# Audio.net
KiCad netlist of a schematic drawn in Altium Designer
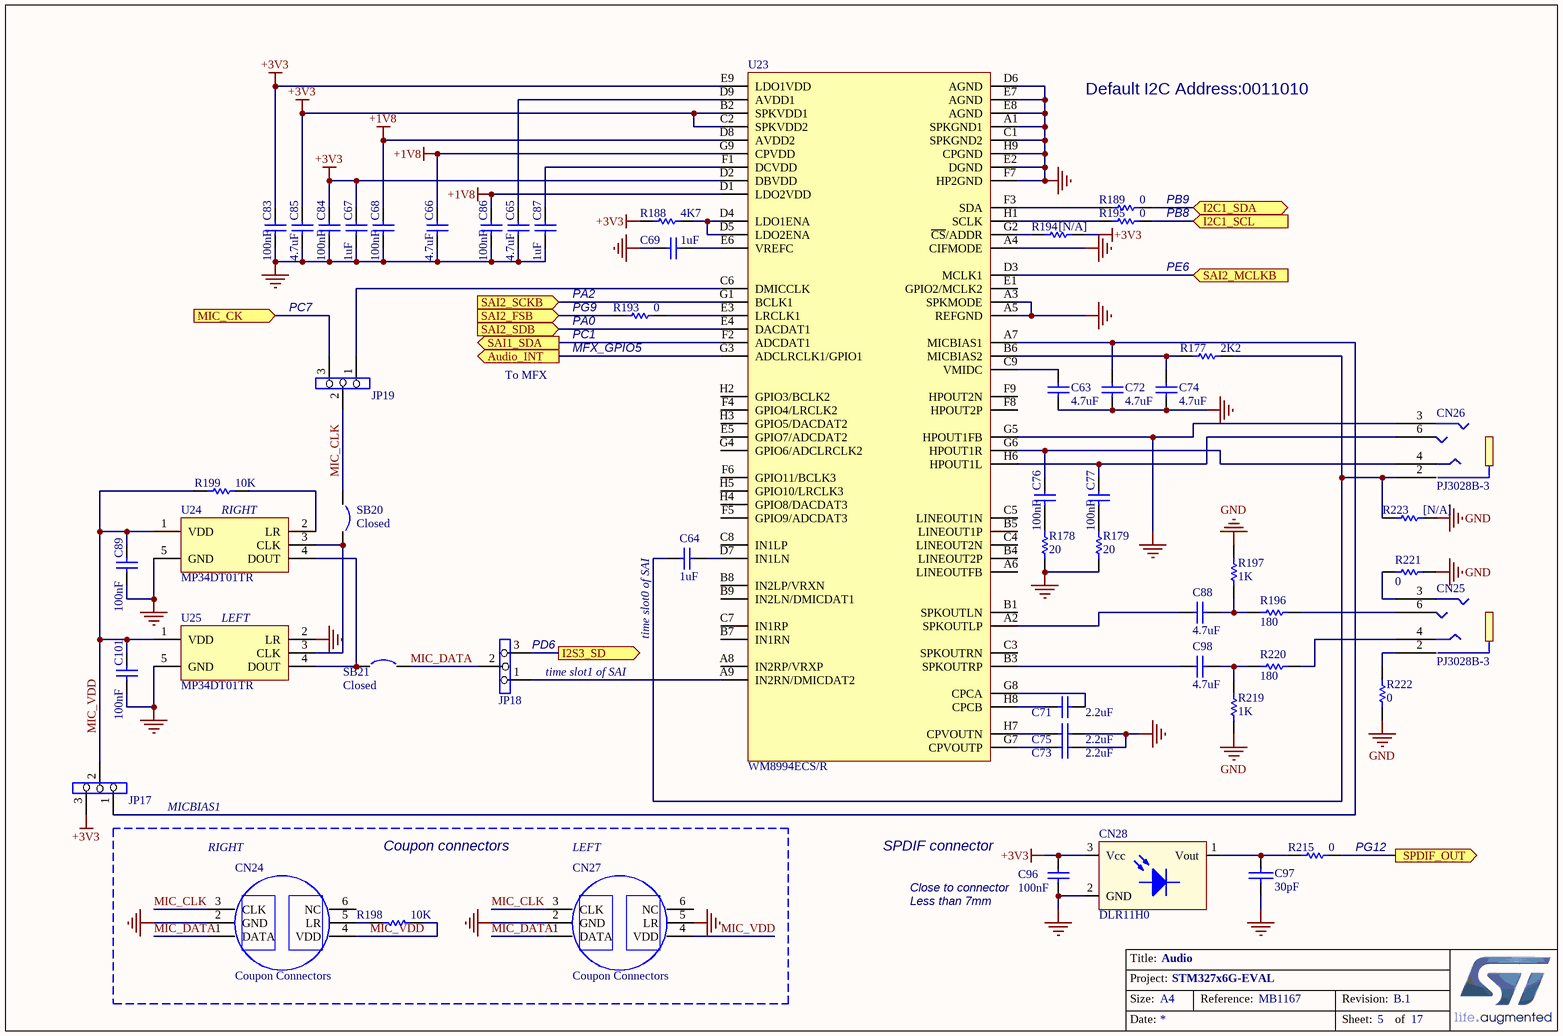
[diagram p0: Audio.SchDoc]

(export (version "E")
  (design (tool "Eeschema 10.0.6"))
  (components
    (comp (ref "C63")
      (value "4.7uF")
      (footprint "0603C")
      (description "Capacitor")
      (fields (field (name "PUBLISHER") "Altium Limited"))
      (libsource (lib "Miscellaneous Devices") (part "Cap"))
    )
    (comp (ref "C64")
      (value "1uF")
      (footprint "0603C")
      (description "Capacitor")
      (fields (field (name "PUBLISHER") "Altium Limited"))
      (libsource (lib "Miscellaneous Devices") (part "CAP"))
    )
    (comp (ref "C65")
      (value "4.7uF")
      (footprint "0603C")
      (description "Capacitor")
      (fields (field (name "PUBLISHER") "Altium Limited"))
      (libsource (lib "Miscellaneous Devices") (part "Cap"))
    )
    (comp (ref "C66")
      (value "4.7uF")
      (footprint "0603C")
      (description "Capacitor")
      (fields (field (name "PUBLISHER") "Altium Limited"))
      (libsource (lib "Miscellaneous Devices") (part "Cap"))
    )
    (comp (ref "C67")
      (value "1uF")
      (footprint "0603C")
      (description "Capacitor")
      (fields (field (name "PUBLISHER") "Altium Limited"))
      (libsource (lib "Miscellaneous Devices") (part "CAP"))
    )
    (comp (ref "C68")
      (value "100nF")
      (footprint "0603C")
      (description "Capacitor")
      (fields (field (name "PUBLISHER") "Altium Limited"))
      (libsource (lib "Miscellaneous Devices") (part "Cap"))
    )
    (comp (ref "C69")
      (value "1uF")
      (footprint "0603C")
      (description "Capacitor")
      (fields (field (name "PUBLISHER") "Altium Limited"))
      (libsource (lib "Miscellaneous Devices") (part "CAP"))
    )
    (comp (ref "C71")
      (value "2.2uF")
      (footprint "0603C")
      (description "Capacitor")
      (fields (field (name "PUBLISHER") "Altium Limited"))
      (libsource (lib "Miscellaneous Devices") (part "CAP"))
    )
    (comp (ref "C72")
      (value "4.7uF")
      (footprint "0603C")
      (description "Capacitor")
      (fields (field (name "PUBLISHER") "Altium Limited"))
      (libsource (lib "Miscellaneous Devices") (part "Cap"))
    )
    (comp (ref "C73")
      (value "2.2uF")
      (footprint "0603C")
      (description "Capacitor")
      (fields (field (name "PUBLISHER") "Altium Limited"))
      (libsource (lib "Miscellaneous Devices") (part "CAP"))
    )
    (comp (ref "C74")
      (value "4.7uF")
      (footprint "0603C")
      (description "Capacitor")
      (fields (field (name "PUBLISHER") "Altium Limited"))
      (libsource (lib "Miscellaneous Devices") (part "Cap"))
    )
    (comp (ref "C75")
      (value "2.2uF")
      (footprint "0603C")
      (description "Capacitor")
      (fields (field (name "PUBLISHER") "Altium Limited"))
      (libsource (lib "Miscellaneous Devices") (part "CAP"))
    )
    (comp (ref "C76")
      (value "100nF")
      (footprint "0603C")
      (description "Capacitor")
      (fields (field (name "PUBLISHER") "Altium Limited"))
      (libsource (lib "Miscellaneous Devices") (part "Cap"))
    )
    (comp (ref "C77")
      (value "100nF")
      (footprint "0603C")
      (description "Capacitor")
      (fields (field (name "PUBLISHER") "Altium Limited"))
      (libsource (lib "Miscellaneous Devices") (part "Cap"))
    )
    (comp (ref "C83")
      (value "100nF")
      (footprint "0603C")
      (description "Capacitor")
      (fields (field (name "PUBLISHER") "Altium Limited"))
      (libsource (lib "Miscellaneous Devices") (part "Cap"))
    )
    (comp (ref "C84")
      (value "100nF")
      (footprint "0603C")
      (description "Capacitor")
      (fields (field (name "PUBLISHER") "Altium Limited"))
      (libsource (lib "Miscellaneous Devices") (part "Cap"))
    )
    (comp (ref "C85")
      (value "4.7uF")
      (footprint "0603C")
      (description "Capacitor")
      (fields (field (name "PUBLISHER") "Altium Limited"))
      (libsource (lib "Miscellaneous Devices") (part "Cap"))
    )
    (comp (ref "C86")
      (value "100nF")
      (footprint "0603C")
      (description "Capacitor")
      (fields (field (name "PUBLISHER") "Altium Limited"))
      (libsource (lib "Miscellaneous Devices") (part "Cap"))
    )
    (comp (ref "C87")
      (value "1uF")
      (footprint "0603C")
      (description "Capacitor")
      (fields (field (name "PUBLISHER") "Altium Limited"))
      (libsource (lib "Miscellaneous Devices") (part "CAP"))
    )
    (comp (ref "C88")
      (value "4.7uF")
      (footprint "0603C")
      (description "Capacitor")
      (fields (field (name "PUBLISHER") "Altium Limited"))
      (libsource (lib "Miscellaneous Devices") (part "Cap"))
    )
    (comp (ref "C89")
      (value "100nF")
      (footprint "0603C")
      (description "Capacitor")
      (fields (field (name "PUBLISHER") "Altium Limited"))
      (libsource (lib "Miscellaneous Devices") (part "Cap"))
    )
    (comp (ref "C96")
      (value "100nF")
      (footprint "0603C")
      (description "Capacitor")
      (fields (field (name "PUBLISHER") "Altium Limited"))
      (libsource (lib "Miscellaneous Devices") (part "Cap"))
    )
    (comp (ref "C97")
      (value "30pF")
      (footprint "0603C")
      (description "Capacitor")
      (libsource (lib "*") (part "CAP"))
    )
    (comp (ref "C98")
      (value "4.7uF")
      (footprint "0603C")
      (description "Capacitor")
      (fields (field (name "PUBLISHER") "Altium Limited"))
      (libsource (lib "Miscellaneous Devices") (part "Cap"))
    )
    (comp (ref "C101")
      (value "100nF")
      (footprint "0603C")
      (description "Capacitor")
      (fields (field (name "PUBLISHER") "Altium Limited"))
      (libsource (lib "Miscellaneous Devices") (part "Cap"))
    )
    (comp (ref "CN24")
      (value "Coupon Connectors")
      (footprint "Coupon")
      (description "Header, 3-Pin, Single row")
      (fields (field (name "PUBLISHER") "Altium Limited"))
      (libsource (lib "MB1167") (part "Coupon Connectors"))
    )
    (comp (ref "CN25") (value "PJ3028B-3") (footprint "PJ3028B") (libsource (lib "MB786") (part "PJ3028B-3")))
    (comp (ref "CN26") (value "PJ3028B-3") (footprint "PJ3028B") (libsource (lib "MB786") (part "PJ3028B-3")))
    (comp (ref "CN27")
      (value "Coupon Connectors")
      (footprint "Coupon")
      (description "Header, 3-Pin, Single row")
      (fields (field (name "PUBLISHER") "Altium Limited"))
      (libsource (lib "MB1167") (part "Coupon Connectors"))
    )
    (comp (ref "CN28")
      (value "DLR11H0")
      (footprint "CONN_DLR11H0")
      (libsource (lib "MB1167_1") (part "OPTO"))
    )
    (comp (ref "JP17") (value "~") (footprint "SIP3") (libsource (lib "STR910_SCHLIB") (part "Jumper3")))
    (comp (ref "JP18") (value "~") (footprint "SIP3") (libsource (lib "STR910_SCHLIB") (part "Jumper3")))
    (comp (ref "JP19") (value "~") (footprint "SIP3") (libsource (lib "STR910_SCHLIB") (part "Jumper3")))
    (comp (ref "R177")
      (value "2K2")
      (footprint "0603R")
      (description "Resistor")
      (fields (field (name "PUBLISHER") "Altium Limited"))
      (libsource (lib "Miscellaneous Devices") (part "Res1"))
    )
    (comp (ref "R178")
      (value "20")
      (footprint "0603R")
      (description "Resistor")
      (fields (field (name "PUBLISHER") "Altium Limited"))
      (libsource (lib "Miscellaneous Devices") (part "Res1"))
    )
    (comp (ref "R179")
      (value "20")
      (footprint "0603R")
      (description "Resistor")
      (fields (field (name "PUBLISHER") "Altium Limited"))
      (libsource (lib "Miscellaneous Devices") (part "Res1"))
    )
    (comp (ref "R188")
      (value "4K7")
      (footprint "0603R")
      (description "Resistor")
      (fields (field (name "PUBLISHER") "Altium Limited"))
      (libsource (lib "Miscellaneous Devices") (part "Res1"))
    )
    (comp (ref "R189")
      (value "0")
      (footprint "0603R")
      (description "Resistor")
      (fields (field (name "PUBLISHER") "Altium Limited"))
      (libsource (lib "Miscellaneous Devices") (part "Res1"))
    )
    (comp (ref "R193")
      (value "0")
      (footprint "0603R")
      (description "Resistor")
      (fields (field (name "PUBLISHER") "Altium Limited"))
      (libsource (lib "Miscellaneous Devices") (part "Res1"))
    )
    (comp (ref "R194")
      (value "[N/A]")
      (footprint "0603R")
      (description "Resistor")
      (fields (field (name "PUBLISHER") "Altium Limited"))
      (libsource (lib "Miscellaneous Devices") (part "Res1"))
    )
    (comp (ref "R195")
      (value "0")
      (footprint "0603R")
      (description "Resistor")
      (fields (field (name "PUBLISHER") "Altium Limited"))
      (libsource (lib "Miscellaneous Devices") (part "Res1"))
    )
    (comp (ref "R196")
      (value "180")
      (footprint "0402R")
      (description "Resistor")
      (fields (field (name "PUBLISHER") "Altium Limited"))
      (libsource (lib "Miscellaneous Devices") (part "Res1"))
    )
    (comp (ref "R197")
      (value "1K")
      (footprint "0402R")
      (description "Resistor")
      (fields (field (name "PUBLISHER") "Altium Limited"))
      (libsource (lib "Miscellaneous Devices") (part "Res1"))
    )
    (comp (ref "R198")
      (value "10K")
      (footprint "0603R")
      (description "Resistor")
      (fields (field (name "PUBLISHER") "Altium Limited"))
      (libsource (lib "Miscellaneous Devices") (part "Res1"))
    )
    (comp (ref "R199")
      (value "10K")
      (footprint "0603R")
      (description "Resistor")
      (fields (field (name "PUBLISHER") "Altium Limited"))
      (libsource (lib "Miscellaneous Devices") (part "Res1"))
    )
    (comp (ref "R215")
      (value "0")
      (footprint "0603R")
      (description "Resistor")
      (fields (field (name "PUBLISHER") "Altium Limited"))
      (libsource (lib "Miscellaneous Devices") (part "Res1"))
    )
    (comp (ref "R219")
      (value "1K")
      (footprint "0402R")
      (description "Resistor")
      (fields (field (name "PUBLISHER") "Altium Limited"))
      (libsource (lib "Miscellaneous Devices") (part "Res1"))
    )
    (comp (ref "R220")
      (value "180")
      (footprint "0402R")
      (description "Resistor")
      (fields (field (name "PUBLISHER") "Altium Limited"))
      (libsource (lib "Miscellaneous Devices") (part "Res1"))
    )
    (comp (ref "R221")
      (value "0")
      (footprint "0603R")
      (description "Resistor")
      (fields (field (name "PUBLISHER") "Altium Limited"))
      (libsource (lib "Miscellaneous Devices") (part "Res1"))
    )
    (comp (ref "R222")
      (value "0")
      (footprint "0603R")
      (description "Resistor")
      (fields (field (name "PUBLISHER") "Altium Limited"))
      (libsource (lib "Miscellaneous Devices") (part "Res1"))
    )
    (comp (ref "R223")
      (value "[N/A]")
      (footprint "0603R")
      (description "Resistor")
      (fields (field (name "PUBLISHER") "Altium Limited"))
      (libsource (lib "Miscellaneous Devices") (part "Res1"))
    )
    (comp (ref "SB20")
      (value "Closed")
      (footprint "SB_0603")
      (description "Circuit Breaker")
      (fields (field (name "PUBLISHER") "Altium Limited"))
      (libsource (lib "MB1167") (part "Circuit Breaker_close"))
    )
    (comp (ref "SB21")
      (value "Closed")
      (footprint "SB_0603")
      (description "Circuit Breaker")
      (fields (field (name "PUBLISHER") "Altium Limited"))
      (libsource (lib "MB1167") (part "Circuit Breaker_close"))
    )
    (comp (ref "U23")
      (value "WM8994ECS/R")
      (footprint "BGA72_0R5_4R5X4")
      (libsource (lib "mb1045") (part "WM8994ECS/R"))
    )
    (comp (ref "U24")
      (value "MP34DT01TR")
      (footprint "MP34DT01TR")
      (description "MEMS audio sensor")
      (fields (field (name "PUBLISHER") "Altium Limited"))
      (libsource (lib "mb1045") (part "MP34DT01TR"))
    )
    (comp (ref "U25")
      (value "MP34DT01TR")
      (footprint "MP34DT01TR")
      (description "MEMS audio sensor")
      (fields (field (name "PUBLISHER") "Altium Limited"))
      (libsource (lib "mb1045") (part "MP34DT01TR"))
    )
  )
  (nets
    (net (code "1") (name "+1V8") (class "Default")
      (node (ref "C66") (pin "1") (pinfunction "1_1") (pintype "passive"))
      (node (ref "C68") (pin "1") (pinfunction "1_1") (pintype "passive"))
      (node (ref "C86") (pin "1") (pinfunction "1_1") (pintype "passive"))
      (node (ref "U23") (pin "D1") (pinfunction "LDO2VDD_D1") (pintype "passive"))
      (node (ref "U23") (pin "D8") (pinfunction "AVDD2_D8") (pintype "passive"))
      (node (ref "U23") (pin "G9") (pinfunction "CPVDD_G9") (pintype "passive"))
    )
    (net (code "2") (name "+3V3") (class "Default")
      (node (ref "C67") (pin "1") (pinfunction "1_1") (pintype "passive"))
      (node (ref "C83") (pin "1") (pinfunction "1_1") (pintype "passive"))
      (node (ref "C84") (pin "1") (pinfunction "1_1") (pintype "passive"))
      (node (ref "C85") (pin "1") (pinfunction "1_1") (pintype "passive"))
      (node (ref "C96") (pin "2") (pinfunction "2_2") (pintype "passive"))
      (node (ref "CN28") (pin "3") (pinfunction "Vcc_3") (pintype "passive"))
      (node (ref "JP17") (pin "3") (pintype "passive"))
      (node (ref "R188") (pin "2") (pinfunction "2_2") (pintype "passive"))
      (node (ref "R194") (pin "1") (pinfunction "1_1") (pintype "passive"))
      (node (ref "U23") (pin "B2") (pinfunction "SPKVDD1_B2") (pintype "passive"))
      (node (ref "U23") (pin "C2") (pinfunction "SPKVDD2_C2") (pintype "passive"))
      (node (ref "U23") (pin "D2") (pinfunction "DBVDD_D2") (pintype "passive"))
      (node (ref "U23") (pin "E9") (pinfunction "LDO1VDD_E9") (pintype "passive"))
    )
    (net (code "3") (name "/Audio_INT") (class "Default")
      (node (ref "U23") (pin "G3") (pinfunction "ADCLRCLK1/GPIO1_G3") (pintype "passive"))
    )
    (net (code "4") (name "/I2C1_SCL") (class "Default")
      (node (ref "R195") (pin "1") (pinfunction "1_1") (pintype "passive"))
    )
    (net (code "5") (name "/I2C1_SDA") (class "Default")
      (node (ref "R189") (pin "1") (pinfunction "1_1") (pintype "passive"))
    )
    (net (code "6") (name "/I2S3_SD") (class "Default") (node (ref "JP18") (pin "3") (pintype "passive")))
    (net (code "7") (name "/MIC_CK") (class "Default") (node (ref "JP19") (pin "3") (pintype "passive")))
    (net (code "8") (name "/MIC_CLK") (class "Default")
      (node (ref "CN24") (pin "3") (pinfunction "CLK_3") (pintype "passive"))
      (node (ref "CN27") (pin "3") (pinfunction "CLK_3") (pintype "passive"))
      (node (ref "JP19") (pin "2") (pintype "passive"))
      (node (ref "SB20") (pin "1") (pinfunction "1_1") (pintype "passive"))
    )
    (net (code "9") (name "/MIC_DATA") (class "Default")
      (node (ref "CN24") (pin "1") (pinfunction "DATA_1") (pintype "passive"))
      (node (ref "CN27") (pin "1") (pinfunction "DATA_1") (pintype "passive"))
      (node (ref "JP18") (pin "2") (pintype "passive"))
      (node (ref "SB21") (pin "2") (pinfunction "2_2") (pintype "passive"))
    )
    (net (code "10") (name "/MIC_VDD") (class "Default")
      (node (ref "C101") (pin "1") (pinfunction "1_1") (pintype "passive"))
      (node (ref "C89") (pin "1") (pinfunction "1_1") (pintype "passive"))
      (node (ref "CN24") (pin "4") (pinfunction "VDD_4") (pintype "passive"))
      (node (ref "CN27") (pin "4") (pinfunction "VDD_4") (pintype "passive"))
      (node (ref "JP17") (pin "2") (pintype "passive"))
      (node (ref "R198") (pin "2") (pinfunction "2_2") (pintype "passive"))
      (node (ref "R199") (pin "2") (pinfunction "2_2") (pintype "passive"))
      (node (ref "U24") (pin "1") (pinfunction "VDD_1") (pintype "passive"))
      (node (ref "U25") (pin "1") (pinfunction "VDD_1") (pintype "passive"))
    )
    (net (code "11") (name "/SAI1_SDA") (class "Default")
      (node (ref "U23") (pin "F2") (pinfunction "ADCDAT1_F2") (pintype "passive"))
    )
    (net (code "12") (name "/SAI2_FSB") (class "Default")
      (node (ref "R193") (pin "2") (pinfunction "2_2") (pintype "passive"))
    )
    (net (code "13") (name "/SAI2_MCLKB") (class "Default")
      (node (ref "U23") (pin "D3") (pinfunction "MCLK1_D3") (pintype "passive"))
    )
    (net (code "14") (name "/SAI2_SCKB") (class "Default")
      (node (ref "U23") (pin "G1") (pinfunction "BCLK1_G1") (pintype "passive"))
    )
    (net (code "15") (name "/SAI2_SDB") (class "Default")
      (node (ref "U23") (pin "E4") (pinfunction "DACDAT1_E4") (pintype "passive"))
    )
    (net (code "16") (name "/SPDIF_OUT") (class "Default")
      (node (ref "R215") (pin "1") (pinfunction "1_1") (pintype "passive"))
    )
    (net (code "17") (name "GND") (class "Default")
      (node (ref "C101") (pin "2") (pinfunction "2_2") (pintype "passive"))
      (node (ref "C63") (pin "1") (pinfunction "1_1") (pintype "passive"))
      (node (ref "C65") (pin "2") (pinfunction "2_2") (pintype "passive"))
      (node (ref "C66") (pin "2") (pinfunction "2_2") (pintype "passive"))
      (node (ref "C67") (pin "2") (pinfunction "2_2") (pintype "passive"))
      (node (ref "C68") (pin "2") (pinfunction "2_2") (pintype "passive"))
      (node (ref "C69") (pin "2") (pinfunction "2_2") (pintype "passive"))
      (node (ref "C72") (pin "1") (pinfunction "1_1") (pintype "passive"))
      (node (ref "C73") (pin "2") (pinfunction "2_2") (pintype "passive"))
      (node (ref "C74") (pin "1") (pinfunction "1_1") (pintype "passive"))
      (node (ref "C75") (pin "2") (pinfunction "2_2") (pintype "passive"))
      (node (ref "C83") (pin "2") (pinfunction "2_2") (pintype "passive"))
      (node (ref "C84") (pin "2") (pinfunction "2_2") (pintype "passive"))
      (node (ref "C85") (pin "2") (pinfunction "2_2") (pintype "passive"))
      (node (ref "C86") (pin "2") (pinfunction "2_2") (pintype "passive"))
      (node (ref "C87") (pin "2") (pinfunction "2_2") (pintype "passive"))
      (node (ref "C89") (pin "2") (pinfunction "2_2") (pintype "passive"))
      (node (ref "C96") (pin "1") (pinfunction "1_1") (pintype "passive"))
      (node (ref "C97") (pin "2") (pinfunction "2_2") (pintype "passive"))
      (node (ref "CN24") (pin "2") (pinfunction "GND_2") (pintype "passive"))
      (node (ref "CN26") (pin "3") (pintype "passive"))
      (node (ref "CN27") (pin "2") (pinfunction "GND_2") (pintype "passive"))
      (node (ref "CN27") (pin "5") (pinfunction "LR_5") (pintype "passive"))
      (node (ref "CN28") (pin "2") (pinfunction "GND_2") (pintype "passive"))
      (node (ref "R178") (pin "2") (pinfunction "2_2") (pintype "passive"))
      (node (ref "R179") (pin "2") (pinfunction "2_2") (pintype "passive"))
      (node (ref "R197") (pin "2") (pinfunction "2_2") (pintype "passive"))
      (node (ref "R219") (pin "1") (pinfunction "1_1") (pintype "passive"))
      (node (ref "R221") (pin "2") (pinfunction "2_2") (pintype "passive"))
      (node (ref "R222") (pin "2") (pinfunction "2_2") (pintype "passive"))
      (node (ref "R223") (pin "1") (pinfunction "1_1") (pintype "passive"))
      (node (ref "U23") (pin "A1") (pinfunction "SPKGND1_A1") (pintype "passive"))
      (node (ref "U23") (pin "A3") (pinfunction "SPKMODE_A3") (pintype "passive"))
      (node (ref "U23") (pin "A4") (pinfunction "CIFMODE_A4") (pintype "passive"))
      (node (ref "U23") (pin "A5") (pinfunction "REFGND_A5") (pintype "passive"))
      (node (ref "U23") (pin "C1") (pinfunction "SPKGND2_C1") (pintype "passive"))
      (node (ref "U23") (pin "D6") (pinfunction "AGND_D6") (pintype "passive"))
      (node (ref "U23") (pin "E2") (pinfunction "DGND_E2") (pintype "passive"))
      (node (ref "U23") (pin "E7") (pinfunction "AGND_E7") (pintype "passive"))
      (node (ref "U23") (pin "E8") (pinfunction "AGND_E8") (pintype "passive"))
      (node (ref "U23") (pin "F7") (pinfunction "HP2GND_F7") (pintype "passive"))
      (node (ref "U23") (pin "G5") (pinfunction "HPOUT1FB_G5") (pintype "passive"))
      (node (ref "U23") (pin "H9") (pinfunction "CPGND_H9") (pintype "passive"))
      (node (ref "U24") (pin "5") (pinfunction "GND_5") (pintype "passive"))
      (node (ref "U25") (pin "2") (pinfunction "LR_2") (pintype "passive"))
      (node (ref "U25") (pin "5") (pinfunction "GND_5") (pintype "passive"))
    )
    (net (code "18") (name "Net-(C64-Pad2)") (class "Default")
      (node (ref "C64") (pin "2") (pinfunction "2_2") (pintype "passive"))
      (node (ref "CN26") (pin "2") (pintype "passive"))
      (node (ref "R177") (pin "1") (pinfunction "1_1") (pintype "passive"))
      (node (ref "R223") (pin "2") (pinfunction "2_2") (pintype "passive"))
    )
    (net (code "19") (name "Net-(C76-Pad2)") (class "Default")
      (node (ref "C76") (pin "2") (pinfunction "2_2") (pintype "passive"))
      (node (ref "R178") (pin "1") (pinfunction "1_1") (pintype "passive"))
    )
    (net (code "20") (name "Net-(C77-Pad2)") (class "Default")
      (node (ref "C77") (pin "2") (pinfunction "2_2") (pintype "passive"))
      (node (ref "R179") (pin "1") (pinfunction "1_1") (pintype "passive"))
    )
    (net (code "21") (name "Net-(C88-Pad1)") (class "Default")
      (node (ref "C88") (pin "1") (pinfunction "1_1") (pintype "passive"))
      (node (ref "R196") (pin "1") (pinfunction "1_1") (pintype "passive"))
      (node (ref "R197") (pin "1") (pinfunction "1_1") (pintype "passive"))
    )
    (net (code "22") (name "Net-(C98-Pad1)") (class "Default")
      (node (ref "C98") (pin "1") (pinfunction "1_1") (pintype "passive"))
      (node (ref "R219") (pin "2") (pinfunction "2_2") (pintype "passive"))
      (node (ref "R220") (pin "2") (pinfunction "2_2") (pintype "passive"))
    )
    (net (code "23") (name "Net-(CN24-LR)") (class "Default")
      (node (ref "CN24") (pin "5") (pinfunction "LR_5") (pintype "passive"))
      (node (ref "R198") (pin "1") (pinfunction "1_1") (pintype "passive"))
    )
    (net (code "24") (name "Net-(CN25-Pad2)") (class "Default")
      (node (ref "CN25") (pin "2") (pintype "passive"))
      (node (ref "R222") (pin "1") (pinfunction "1_1") (pintype "passive"))
    )
    (net (code "25") (name "Net-(CN25-Pad3)") (class "Default")
      (node (ref "CN25") (pin "3") (pintype "passive"))
      (node (ref "R221") (pin "1") (pinfunction "1_1") (pintype "passive"))
    )
    (net (code "26") (name "Net-(CN25-Pad4)") (class "Default")
      (node (ref "CN25") (pin "4") (pintype "passive"))
      (node (ref "R220") (pin "1") (pinfunction "1_1") (pintype "passive"))
    )
    (net (code "27") (name "Net-(CN25-Pad6)") (class "Default")
      (node (ref "CN25") (pin "6") (pintype "passive"))
      (node (ref "R196") (pin "2") (pinfunction "2_2") (pintype "passive"))
    )
    (net (code "28") (name "Net-(CN28-Vout)") (class "Default")
      (node (ref "C97") (pin "1") (pinfunction "1_1") (pintype "passive"))
      (node (ref "CN28") (pin "1") (pinfunction "Vout_1") (pintype "passive"))
      (node (ref "R215") (pin "2") (pinfunction "2_2") (pintype "passive"))
    )
    (net (code "29") (name "Net-(U23-AVDD1)") (class "Default")
      (node (ref "C65") (pin "1") (pinfunction "1_1") (pintype "passive"))
      (node (ref "U23") (pin "D9") (pinfunction "AVDD1_D9") (pintype "passive"))
    )
    (net (code "30") (name "Net-(U23-CPCA)") (class "Default")
      (node (ref "C71") (pin "2") (pinfunction "2_2") (pintype "passive"))
      (node (ref "U23") (pin "G8") (pinfunction "CPCA_G8") (pintype "passive"))
    )
    (net (code "31") (name "Net-(U23-CPCB)") (class "Default")
      (node (ref "C71") (pin "1") (pinfunction "1_1") (pintype "passive"))
      (node (ref "U23") (pin "H8") (pinfunction "CPCB_H8") (pintype "passive"))
    )
    (net (code "32") (name "Net-(U23-CPVOUTN)") (class "Default")
      (node (ref "C75") (pin "1") (pinfunction "1_1") (pintype "passive"))
      (node (ref "U23") (pin "H7") (pinfunction "CPVOUTN_H7") (pintype "passive"))
    )
    (net (code "33") (name "Net-(U23-CPVOUTP)") (class "Default")
      (node (ref "C73") (pin "1") (pinfunction "1_1") (pintype "passive"))
      (node (ref "U23") (pin "G7") (pinfunction "CPVOUTP_G7") (pintype "passive"))
    )
    (net (code "34") (name "Net-(U23-DCVDD)") (class "Default")
      (node (ref "C87") (pin "1") (pinfunction "1_1") (pintype "passive"))
      (node (ref "U23") (pin "F1") (pinfunction "DCVDD_F1") (pintype "passive"))
    )
    (net (code "35") (name "Net-(U23-DMICCLK)") (class "Default")
      (node (ref "JP19") (pin "1") (pintype "passive"))
      (node (ref "U23") (pin "C6") (pinfunction "DMICCLK_C6") (pintype "passive"))
    )
    (net (code "36") (name "Net-(U23-HPOUT1L)") (class "Default")
      (node (ref "C77") (pin "1") (pinfunction "1_1") (pintype "passive"))
      (node (ref "CN26") (pin "6") (pintype "passive"))
      (node (ref "U23") (pin "H6") (pinfunction "HPOUT1L_H6") (pintype "passive"))
    )
    (net (code "37") (name "Net-(U23-HPOUT1R)") (class "Default")
      (node (ref "C76") (pin "1") (pinfunction "1_1") (pintype "passive"))
      (node (ref "CN26") (pin "4") (pintype "passive"))
      (node (ref "U23") (pin "G6") (pinfunction "HPOUT1R_G6") (pintype "passive"))
    )
    (net (code "38") (name "Net-(U23-IN1LN)") (class "Default")
      (node (ref "C64") (pin "1") (pinfunction "1_1") (pintype "passive"))
      (node (ref "U23") (pin "D7") (pinfunction "IN1LN_D7") (pintype "passive"))
    )
    (net (code "39") (name "Net-(U23-IN2RN{slash}DMICDAT2)") (class "Default")
      (node (ref "JP18") (pin "1") (pintype "passive"))
      (node (ref "U23") (pin "A9") (pinfunction "IN2RN/DMICDAT2_A9") (pintype "passive"))
    )
    (net (code "40") (name "Net-(U23-LDO1ENA)") (class "Default")
      (node (ref "R188") (pin "1") (pinfunction "1_1") (pintype "passive"))
      (node (ref "U23") (pin "D4") (pinfunction "LDO1ENA_D4") (pintype "passive"))
      (node (ref "U23") (pin "D5") (pinfunction "LDO2ENA_D5") (pintype "passive"))
    )
    (net (code "41") (name "Net-(U23-LRCLK1)") (class "Default")
      (node (ref "R193") (pin "1") (pinfunction "1_1") (pintype "passive"))
      (node (ref "U23") (pin "E3") (pinfunction "LRCLK1_E3") (pintype "passive"))
    )
    (net (code "42") (name "Net-(U23-MICBIAS1)") (class "Default")
      (node (ref "C72") (pin "2") (pinfunction "2_2") (pintype "passive"))
      (node (ref "JP17") (pin "1") (pintype "passive"))
      (node (ref "U23") (pin "A7") (pinfunction "MICBIAS1_A7") (pintype "passive"))
    )
    (net (code "43") (name "Net-(U23-MICBIAS2)") (class "Default")
      (node (ref "C74") (pin "2") (pinfunction "2_2") (pintype "passive"))
      (node (ref "R177") (pin "2") (pinfunction "2_2") (pintype "passive"))
      (node (ref "U23") (pin "B6") (pinfunction "MICBIAS2_B6") (pintype "passive"))
    )
    (net (code "44") (name "Net-(U23-SCLK)") (class "Default")
      (node (ref "R195") (pin "2") (pinfunction "2_2") (pintype "passive"))
      (node (ref "U23") (pin "H1") (pinfunction "SCLK_H1") (pintype "passive"))
    )
    (net (code "45") (name "Net-(U23-SDA)") (class "Default")
      (node (ref "R189") (pin "2") (pinfunction "2_2") (pintype "passive"))
      (node (ref "U23") (pin "F3") (pinfunction "SDA_F3") (pintype "passive"))
    )
    (net (code "46") (name "Net-(U23-SPKOUTLP)") (class "Default")
      (node (ref "C88") (pin "2") (pinfunction "2_2") (pintype "passive"))
      (node (ref "U23") (pin "A2") (pinfunction "SPKOUTLP_A2") (pintype "passive"))
    )
    (net (code "47") (name "Net-(U23-SPKOUTRP)") (class "Default")
      (node (ref "C98") (pin "2") (pinfunction "2_2") (pintype "passive"))
      (node (ref "U23") (pin "B3") (pinfunction "SPKOUTRP_B3") (pintype "passive"))
    )
    (net (code "48") (name "Net-(U23-VMIDC)") (class "Default")
      (node (ref "C63") (pin "2") (pinfunction "2_2") (pintype "passive"))
      (node (ref "U23") (pin "C9") (pinfunction "VMIDC_C9") (pintype "passive"))
    )
    (net (code "49") (name "Net-(U23-VREFC)") (class "Default")
      (node (ref "C69") (pin "1") (pinfunction "1_1") (pintype "passive"))
      (node (ref "U23") (pin "E6") (pinfunction "VREFC_E6") (pintype "passive"))
    )
    (net (code "50") (name "Net-(U23-~{CS}{slash}ADDR)") (class "Default")
      (node (ref "R194") (pin "2") (pinfunction "2_2") (pintype "passive"))
      (node (ref "U23") (pin "G2") (pinfunction "~{CS}/ADDR_G2") (pintype "passive"))
    )
    (net (code "51") (name "Net-(U24-CLK)") (class "Default")
      (node (ref "SB20") (pin "2") (pinfunction "2_2") (pintype "passive"))
      (node (ref "U24") (pin "3") (pinfunction "CLK_3") (pintype "passive"))
      (node (ref "U25") (pin "3") (pinfunction "CLK_3") (pintype "passive"))
    )
    (net (code "52") (name "Net-(U24-DOUT)") (class "Default")
      (node (ref "SB21") (pin "1") (pinfunction "1_1") (pintype "passive"))
      (node (ref "U24") (pin "4") (pinfunction "DOUT_4") (pintype "passive"))
      (node (ref "U25") (pin "4") (pinfunction "DOUT_4") (pintype "passive"))
    )
    (net (code "53") (name "Net-(U24-LR)") (class "Default")
      (node (ref "R199") (pin "1") (pinfunction "1_1") (pintype "passive"))
      (node (ref "U24") (pin "2") (pinfunction "LR_2") (pintype "passive"))
    )
    (net (code "54") (name "unconnected-(CN24-NC-Pad6)") (class "Default")
      (node (ref "CN24") (pin "6") (pinfunction "NC_6") (pintype "passive"))
    )
    (net (code "55") (name "unconnected-(CN27-NC-Pad6)") (class "Default")
      (node (ref "CN27") (pin "6") (pinfunction "NC_6") (pintype "passive"))
    )
    (net (code "56") (name "unconnected-(U23-GPIO2{slash}MCLK2-PadE1)") (class "Default")
      (node (ref "U23") (pin "E1") (pinfunction "GPIO2/MCLK2_E1") (pintype "passive"))
    )
    (net (code "57") (name "unconnected-(U23-GPIO3{slash}BCLK2-PadH2)") (class "Default")
      (node (ref "U23") (pin "H2") (pinfunction "GPIO3/BCLK2_H2") (pintype "passive"))
    )
    (net (code "58") (name "unconnected-(U23-GPIO4{slash}LRCLK2-PadF4)") (class "Default")
      (node (ref "U23") (pin "F4") (pinfunction "GPIO4/LRCLK2_F4") (pintype "passive"))
    )
    (net (code "59") (name "unconnected-(U23-GPIO5{slash}DACDAT2-PadH3)") (class "Default")
      (node (ref "U23") (pin "H3") (pinfunction "GPIO5/DACDAT2_H3") (pintype "passive"))
    )
    (net (code "60") (name "unconnected-(U23-GPIO6{slash}ADCLRCLK2-PadG4)") (class "Default")
      (node (ref "U23") (pin "G4") (pinfunction "GPIO6/ADCLRCLK2_G4") (pintype "passive"))
    )
    (net (code "61") (name "unconnected-(U23-GPIO7{slash}ADCDAT2-PadE5)") (class "Default")
      (node (ref "U23") (pin "E5") (pinfunction "GPIO7/ADCDAT2_E5") (pintype "passive"))
    )
    (net (code "62") (name "unconnected-(U23-GPIO8{slash}DACDAT3-PadH4)") (class "Default")
      (node (ref "U23") (pin "H4") (pinfunction "GPIO8/DACDAT3_H4") (pintype "passive"))
    )
    (net (code "63") (name "unconnected-(U23-GPIO9{slash}ADCDAT3-PadF5)") (class "Default")
      (node (ref "U23") (pin "F5") (pinfunction "GPIO9/ADCDAT3_F5") (pintype "passive"))
    )
    (net (code "64") (name "unconnected-(U23-GPIO10{slash}LRCLK3-PadH5)") (class "Default")
      (node (ref "U23") (pin "H5") (pinfunction "GPIO10/LRCLK3_H5") (pintype "passive"))
    )
    (net (code "65") (name "unconnected-(U23-GPIO11{slash}BCLK3-PadF6)") (class "Default")
      (node (ref "U23") (pin "F6") (pinfunction "GPIO11/BCLK3_F6") (pintype "passive"))
    )
    (net (code "66") (name "unconnected-(U23-HPOUT2N-PadF9)") (class "Default")
      (node (ref "U23") (pin "F9") (pinfunction "HPOUT2N_F9") (pintype "passive"))
    )
    (net (code "67") (name "unconnected-(U23-HPOUT2P-PadF8)") (class "Default")
      (node (ref "U23") (pin "F8") (pinfunction "HPOUT2P_F8") (pintype "passive"))
    )
    (net (code "68") (name "unconnected-(U23-IN1LP-PadC8)") (class "Default")
      (node (ref "U23") (pin "C8") (pinfunction "IN1LP_C8") (pintype "passive"))
    )
    (net (code "69") (name "unconnected-(U23-IN1RN-PadB7)") (class "Default")
      (node (ref "U23") (pin "B7") (pinfunction "IN1RN_B7") (pintype "passive"))
    )
    (net (code "70") (name "unconnected-(U23-IN1RP-PadC7)") (class "Default")
      (node (ref "U23") (pin "C7") (pinfunction "IN1RP_C7") (pintype "passive"))
    )
    (net (code "71") (name "unconnected-(U23-IN2LN{slash}DMICDAT1-PadB9)") (class "Default")
      (node (ref "U23") (pin "B9") (pinfunction "IN2LN/DMICDAT1_B9") (pintype "passive"))
    )
    (net (code "72") (name "unconnected-(U23-IN2LP{slash}VRXN-PadB8)") (class "Default")
      (node (ref "U23") (pin "B8") (pinfunction "IN2LP/VRXN_B8") (pintype "passive"))
    )
    (net (code "73") (name "unconnected-(U23-IN2RP{slash}VRXP-PadA8)") (class "Default")
      (node (ref "U23") (pin "A8") (pinfunction "IN2RP/VRXP_A8") (pintype "passive"))
    )
    (net (code "74") (name "unconnected-(U23-LINEOUT1N-PadC5)") (class "Default")
      (node (ref "U23") (pin "C5") (pinfunction "LINEOUT1N_C5") (pintype "passive"))
    )
    (net (code "75") (name "unconnected-(U23-LINEOUT1P-PadB5)") (class "Default")
      (node (ref "U23") (pin "B5") (pinfunction "LINEOUT1P_B5") (pintype "passive"))
    )
    (net (code "76") (name "unconnected-(U23-LINEOUT2N-PadC4)") (class "Default")
      (node (ref "U23") (pin "C4") (pinfunction "LINEOUT2N_C4") (pintype "passive"))
    )
    (net (code "77") (name "unconnected-(U23-LINEOUT2P-PadB4)") (class "Default")
      (node (ref "U23") (pin "B4") (pinfunction "LINEOUT2P_B4") (pintype "passive"))
    )
    (net (code "78") (name "unconnected-(U23-LINEOUTFB-PadA6)") (class "Default")
      (node (ref "U23") (pin "A6") (pinfunction "LINEOUTFB_A6") (pintype "passive"))
    )
    (net (code "79") (name "unconnected-(U23-SPKOUTLN-PadB1)") (class "Default")
      (node (ref "U23") (pin "B1") (pinfunction "SPKOUTLN_B1") (pintype "passive"))
    )
    (net (code "80") (name "unconnected-(U23-SPKOUTRN-PadC3)") (class "Default")
      (node (ref "U23") (pin "C3") (pinfunction "SPKOUTRN_C3") (pintype "passive"))
    )
  )
)
